# fdc6326l_breakout_minimal.net
KiCad netlist of a schematic drawn in EAGLE
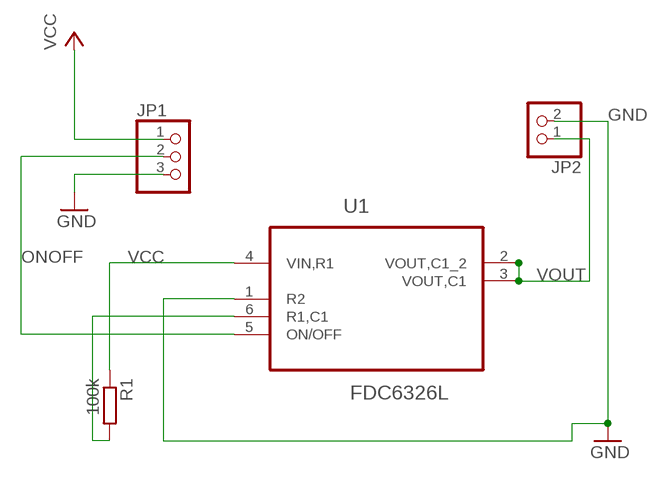
[diagram p0: schematic, sheet 1]

(export (version "E")
  (design (tool "Eeschema 10.0.6"))
  (components
    (comp (ref "JP1")
      (value "PINHD-1X3")
      (footprint "eagle-import:1X03")
      (libsource (lib "eagle-import") (part "PINHD-1X3"))
    )
    (comp (ref "JP2")
      (value "PINHD-1X2")
      (footprint "eagle-import:1X02")
      (libsource (lib "eagle-import") (part "PINHD-1X2"))
    )
    (comp (ref "R1")
      (value "100k")
      (footprint "eagle-import:M0805")
      (libsource (lib "eagle-import") (part "R-EU_M0805"))
    )
    (comp (ref "U1")
      (value "FDC6326L")
      (footprint "eagle-import:SOT95P280X110-6N")
      (libsource (lib "eagle-import") (part "FDC6326L"))
    )
  )
  (nets
    (net (code "1") (name "/ONOFF") (class "Default")
      (node (ref "JP1") (pin "2") (pinfunction "2_2") (pintype "passive"))
      (node (ref "U1") (pin "5") (pinfunction "ON/OFF_5") (pintype "input"))
    )
    (net (code "2") (name "/VOUT") (class "Default")
      (node (ref "JP2") (pin "1") (pinfunction "1_1") (pintype "passive"))
      (node (ref "U1") (pin "2") (pinfunction "VOUT,C1_2_2") (pintype "output"))
      (node (ref "U1") (pin "3") (pinfunction "VOUT,C1_3") (pintype "output"))
    )
    (net (code "3") (name "GND") (class "Default")
      (node (ref "JP1") (pin "3") (pinfunction "3_3") (pintype "passive"))
      (node (ref "JP2") (pin "2") (pinfunction "2_2") (pintype "passive"))
      (node (ref "U1") (pin "1") (pinfunction "R2_1") (pintype "input"))
    )
    (net (code "4") (name "Net-(U1-R1,C1)") (class "Default")
      (node (ref "R1") (pin "2") (pinfunction "2_2") (pintype "passive"))
      (node (ref "U1") (pin "6") (pinfunction "R1,C1_6") (pintype "input"))
    )
    (net (code "5") (name "VCC") (class "Default")
      (node (ref "JP1") (pin "1") (pinfunction "1_1") (pintype "passive"))
      (node (ref "R1") (pin "1") (pinfunction "1_1") (pintype "passive"))
      (node (ref "U1") (pin "4") (pinfunction "VIN,R1_4") (pintype "power_in"))
    )
  )
)
